# DBL_TLC5940_driver_for_High_load_-_5_3A_.net
KiCad netlist of a schematic drawn in Altium Designer
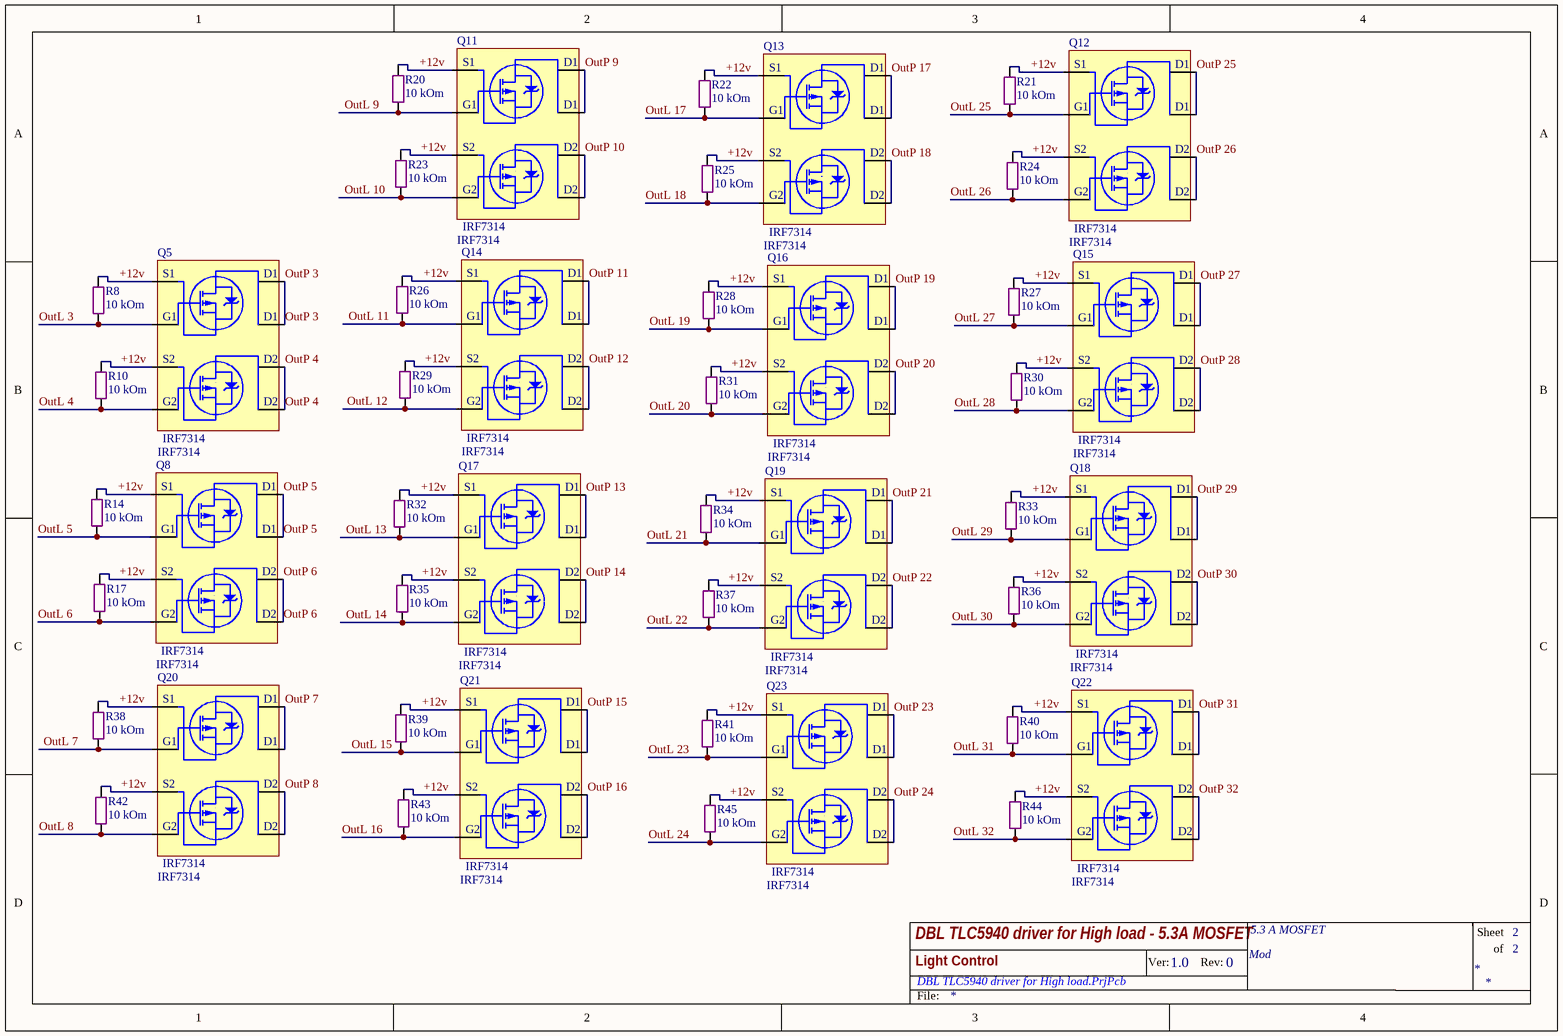
[diagram p0: DBL TLC5940 driver for High load - 5.3A MOSFET.SchDoc]

(export (version "E")
  (design (tool "Eeschema 10.0.6"))
  (components
    (comp (ref "Q5")
      (value "IRF7314")
      (footprint "GeneralCases:SO8")
      (description "Dual P-Ch  20V - 0.058Ω - 5.3A")
      (libsource (lib "Transistor") (part "IRF7314"))
    )
    (comp (ref "Q8")
      (value "IRF7314")
      (footprint "GeneralCases:SO8")
      (description "Dual P-Ch  20V - 0.058Ω - 5.3A")
      (libsource (lib "Transistor") (part "IRF7314"))
    )
    (comp (ref "Q11")
      (value "IRF7314")
      (footprint "GeneralCases:SO8")
      (description "Dual P-Ch  20V - 0.058Ω - 5.3A")
      (libsource (lib "Transistor") (part "IRF7314"))
    )
    (comp (ref "Q12")
      (value "IRF7314")
      (footprint "GeneralCases:SO8")
      (description "Dual P-Ch  20V - 0.058Ω - 5.3A")
      (libsource (lib "Transistor") (part "IRF7314"))
    )
    (comp (ref "Q13")
      (value "IRF7314")
      (footprint "GeneralCases:SO8")
      (description "Dual P-Ch  20V - 0.058Ω - 5.3A")
      (libsource (lib "Transistor") (part "IRF7314"))
    )
    (comp (ref "Q14")
      (value "IRF7314")
      (footprint "GeneralCases:SO8")
      (description "Dual P-Ch  20V - 0.058Ω - 5.3A")
      (libsource (lib "Transistor") (part "IRF7314"))
    )
    (comp (ref "Q15")
      (value "IRF7314")
      (footprint "GeneralCases:SO8")
      (description "Dual P-Ch  20V - 0.058Ω - 5.3A")
      (libsource (lib "Transistor") (part "IRF7314"))
    )
    (comp (ref "Q16")
      (value "IRF7314")
      (footprint "GeneralCases:SO8")
      (description "Dual P-Ch  20V - 0.058Ω - 5.3A")
      (libsource (lib "Transistor") (part "IRF7314"))
    )
    (comp (ref "Q17")
      (value "IRF7314")
      (footprint "GeneralCases:SO8")
      (description "Dual P-Ch  20V - 0.058Ω - 5.3A")
      (libsource (lib "Transistor") (part "IRF7314"))
    )
    (comp (ref "Q18")
      (value "IRF7314")
      (footprint "GeneralCases:SO8")
      (description "Dual P-Ch  20V - 0.058Ω - 5.3A")
      (libsource (lib "Transistor") (part "IRF7314"))
    )
    (comp (ref "Q19")
      (value "IRF7314")
      (footprint "GeneralCases:SO8")
      (description "Dual P-Ch  20V - 0.058Ω - 5.3A")
      (libsource (lib "Transistor") (part "IRF7314"))
    )
    (comp (ref "Q20")
      (value "IRF7314")
      (footprint "GeneralCases:SO8")
      (description "Dual P-Ch  20V - 0.058Ω - 5.3A")
      (libsource (lib "Transistor") (part "IRF7314"))
    )
    (comp (ref "Q21")
      (value "IRF7314")
      (footprint "GeneralCases:SO8")
      (description "Dual P-Ch  20V - 0.058Ω - 5.3A")
      (libsource (lib "Transistor") (part "IRF7314"))
    )
    (comp (ref "Q22")
      (value "IRF7314")
      (footprint "GeneralCases:SO8")
      (description "Dual P-Ch  20V - 0.058Ω - 5.3A")
      (libsource (lib "Transistor") (part "IRF7314"))
    )
    (comp (ref "Q23")
      (value "IRF7314")
      (footprint "GeneralCases:SO8")
      (description "Dual P-Ch  20V - 0.058Ω - 5.3A")
      (libsource (lib "Transistor") (part "IRF7314"))
    )
    (comp (ref "R8")
      (value "10 kOm")
      (footprint "PassiveComponents:SMD 0805 (2012)")
      (libsource (lib "PassiveComponents") (part "Res All Types"))
    )
    (comp (ref "R10")
      (value "10 kOm")
      (footprint "PassiveComponents:SMD 0805 (2012)")
      (libsource (lib "PassiveComponents") (part "Res All Types"))
    )
    (comp (ref "R14")
      (value "10 kOm")
      (footprint "PassiveComponents:SMD 0805 (2012)")
      (libsource (lib "PassiveComponents") (part "Res All Types"))
    )
    (comp (ref "R17")
      (value "10 kOm")
      (footprint "PassiveComponents:SMD 0805 (2012)")
      (libsource (lib "PassiveComponents") (part "Res All Types"))
    )
    (comp (ref "R20")
      (value "10 kOm")
      (footprint "PassiveComponents:SMD 0805 (2012)")
      (libsource (lib "PassiveComponents") (part "Res All Types"))
    )
    (comp (ref "R21")
      (value "10 kOm")
      (footprint "PassiveComponents:SMD 0805 (2012)")
      (libsource (lib "PassiveComponents") (part "Res All Types"))
    )
    (comp (ref "R22")
      (value "10 kOm")
      (footprint "PassiveComponents:SMD 0805 (2012)")
      (libsource (lib "PassiveComponents") (part "Res All Types"))
    )
    (comp (ref "R23")
      (value "10 kOm")
      (footprint "PassiveComponents:SMD 0805 (2012)")
      (libsource (lib "PassiveComponents") (part "Res All Types"))
    )
    (comp (ref "R24")
      (value "10 kOm")
      (footprint "PassiveComponents:SMD 0805 (2012)")
      (libsource (lib "PassiveComponents") (part "Res All Types"))
    )
    (comp (ref "R25")
      (value "10 kOm")
      (footprint "PassiveComponents:SMD 0805 (2012)")
      (libsource (lib "PassiveComponents") (part "Res All Types"))
    )
    (comp (ref "R26")
      (value "10 kOm")
      (footprint "PassiveComponents:SMD 0805 (2012)")
      (libsource (lib "PassiveComponents") (part "Res All Types"))
    )
    (comp (ref "R27")
      (value "10 kOm")
      (footprint "PassiveComponents:SMD 0805 (2012)")
      (libsource (lib "PassiveComponents") (part "Res All Types"))
    )
    (comp (ref "R28")
      (value "10 kOm")
      (footprint "PassiveComponents:SMD 0805 (2012)")
      (libsource (lib "PassiveComponents") (part "Res All Types"))
    )
    (comp (ref "R29")
      (value "10 kOm")
      (footprint "PassiveComponents:SMD 0805 (2012)")
      (libsource (lib "PassiveComponents") (part "Res All Types"))
    )
    (comp (ref "R30")
      (value "10 kOm")
      (footprint "PassiveComponents:SMD 0805 (2012)")
      (libsource (lib "PassiveComponents") (part "Res All Types"))
    )
    (comp (ref "R31")
      (value "10 kOm")
      (footprint "PassiveComponents:SMD 0805 (2012)")
      (libsource (lib "PassiveComponents") (part "Res All Types"))
    )
    (comp (ref "R32")
      (value "10 kOm")
      (footprint "PassiveComponents:SMD 0805 (2012)")
      (libsource (lib "PassiveComponents") (part "Res All Types"))
    )
    (comp (ref "R33")
      (value "10 kOm")
      (footprint "PassiveComponents:SMD 0805 (2012)")
      (libsource (lib "PassiveComponents") (part "Res All Types"))
    )
    (comp (ref "R34")
      (value "10 kOm")
      (footprint "PassiveComponents:SMD 0805 (2012)")
      (libsource (lib "PassiveComponents") (part "Res All Types"))
    )
    (comp (ref "R35")
      (value "10 kOm")
      (footprint "PassiveComponents:SMD 0805 (2012)")
      (libsource (lib "PassiveComponents") (part "Res All Types"))
    )
    (comp (ref "R36")
      (value "10 kOm")
      (footprint "PassiveComponents:SMD 0805 (2012)")
      (libsource (lib "PassiveComponents") (part "Res All Types"))
    )
    (comp (ref "R37")
      (value "10 kOm")
      (footprint "PassiveComponents:SMD 0805 (2012)")
      (libsource (lib "PassiveComponents") (part "Res All Types"))
    )
    (comp (ref "R38")
      (value "10 kOm")
      (footprint "PassiveComponents:SMD 0805 (2012)")
      (libsource (lib "PassiveComponents") (part "Res All Types"))
    )
    (comp (ref "R39")
      (value "10 kOm")
      (footprint "PassiveComponents:SMD 0805 (2012)")
      (libsource (lib "PassiveComponents") (part "Res All Types"))
    )
    (comp (ref "R40")
      (value "10 kOm")
      (footprint "PassiveComponents:SMD 0805 (2012)")
      (libsource (lib "PassiveComponents") (part "Res All Types"))
    )
    (comp (ref "R41")
      (value "10 kOm")
      (footprint "PassiveComponents:SMD 0805 (2012)")
      (libsource (lib "PassiveComponents") (part "Res All Types"))
    )
    (comp (ref "R42")
      (value "10 kOm")
      (footprint "PassiveComponents:SMD 0805 (2012)")
      (libsource (lib "PassiveComponents") (part "Res All Types"))
    )
    (comp (ref "R43")
      (value "10 kOm")
      (footprint "PassiveComponents:SMD 0805 (2012)")
      (libsource (lib "PassiveComponents") (part "Res All Types"))
    )
    (comp (ref "R44")
      (value "10 kOm")
      (footprint "PassiveComponents:SMD 0805 (2012)")
      (libsource (lib "PassiveComponents") (part "Res All Types"))
    )
    (comp (ref "R45")
      (value "10 kOm")
      (footprint "PassiveComponents:SMD 0805 (2012)")
      (libsource (lib "PassiveComponents") (part "Res All Types"))
    )
  )
  (nets
    (net (code "1") (name "/+12v") (class "Default")
      (node (ref "Q11") (pin "1") (pinfunction "S_1") (pintype "passive"))
      (node (ref "Q11") (pin "3") (pinfunction "S_3") (pintype "passive"))
      (node (ref "Q12") (pin "1") (pinfunction "S_1") (pintype "passive"))
      (node (ref "Q12") (pin "3") (pinfunction "S_3") (pintype "passive"))
      (node (ref "Q13") (pin "1") (pinfunction "S_1") (pintype "passive"))
      (node (ref "Q13") (pin "3") (pinfunction "S_3") (pintype "passive"))
      (node (ref "Q14") (pin "1") (pinfunction "S_1") (pintype "passive"))
      (node (ref "Q14") (pin "3") (pinfunction "S_3") (pintype "passive"))
      (node (ref "Q15") (pin "1") (pinfunction "S_1") (pintype "passive"))
      (node (ref "Q15") (pin "3") (pinfunction "S_3") (pintype "passive"))
      (node (ref "Q16") (pin "1") (pinfunction "S_1") (pintype "passive"))
      (node (ref "Q16") (pin "3") (pinfunction "S_3") (pintype "passive"))
      (node (ref "Q17") (pin "1") (pinfunction "S_1") (pintype "passive"))
      (node (ref "Q17") (pin "3") (pinfunction "S_3") (pintype "passive"))
      (node (ref "Q18") (pin "1") (pinfunction "S_1") (pintype "passive"))
      (node (ref "Q18") (pin "3") (pinfunction "S_3") (pintype "passive"))
      (node (ref "Q19") (pin "1") (pinfunction "S_1") (pintype "passive"))
      (node (ref "Q19") (pin "3") (pinfunction "S_3") (pintype "passive"))
      (node (ref "Q20") (pin "1") (pinfunction "S_1") (pintype "passive"))
      (node (ref "Q20") (pin "3") (pinfunction "S_3") (pintype "passive"))
      (node (ref "Q21") (pin "1") (pinfunction "S_1") (pintype "passive"))
      (node (ref "Q21") (pin "3") (pinfunction "S_3") (pintype "passive"))
      (node (ref "Q22") (pin "1") (pinfunction "S_1") (pintype "passive"))
      (node (ref "Q22") (pin "3") (pinfunction "S_3") (pintype "passive"))
      (node (ref "Q23") (pin "1") (pinfunction "S_1") (pintype "passive"))
      (node (ref "Q23") (pin "3") (pinfunction "S_3") (pintype "passive"))
      (node (ref "Q5") (pin "1") (pinfunction "S_1") (pintype "passive"))
      (node (ref "Q5") (pin "3") (pinfunction "S_3") (pintype "passive"))
      (node (ref "Q8") (pin "1") (pinfunction "S_1") (pintype "passive"))
      (node (ref "Q8") (pin "3") (pinfunction "S_3") (pintype "passive"))
      (node (ref "R10") (pin "2") (pinfunction "2_2") (pintype "passive"))
      (node (ref "R14") (pin "2") (pinfunction "2_2") (pintype "passive"))
      (node (ref "R17") (pin "2") (pinfunction "2_2") (pintype "passive"))
      (node (ref "R20") (pin "2") (pinfunction "2_2") (pintype "passive"))
      (node (ref "R21") (pin "2") (pinfunction "2_2") (pintype "passive"))
      (node (ref "R22") (pin "2") (pinfunction "2_2") (pintype "passive"))
      (node (ref "R23") (pin "2") (pinfunction "2_2") (pintype "passive"))
      (node (ref "R24") (pin "2") (pinfunction "2_2") (pintype "passive"))
      (node (ref "R25") (pin "2") (pinfunction "2_2") (pintype "passive"))
      (node (ref "R26") (pin "2") (pinfunction "2_2") (pintype "passive"))
      (node (ref "R27") (pin "2") (pinfunction "2_2") (pintype "passive"))
      (node (ref "R28") (pin "2") (pinfunction "2_2") (pintype "passive"))
      (node (ref "R29") (pin "2") (pinfunction "2_2") (pintype "passive"))
      (node (ref "R30") (pin "2") (pinfunction "2_2") (pintype "passive"))
      (node (ref "R31") (pin "2") (pinfunction "2_2") (pintype "passive"))
      (node (ref "R32") (pin "2") (pinfunction "2_2") (pintype "passive"))
      (node (ref "R33") (pin "2") (pinfunction "2_2") (pintype "passive"))
      (node (ref "R34") (pin "2") (pinfunction "2_2") (pintype "passive"))
      (node (ref "R35") (pin "2") (pinfunction "2_2") (pintype "passive"))
      (node (ref "R36") (pin "2") (pinfunction "2_2") (pintype "passive"))
      (node (ref "R37") (pin "2") (pinfunction "2_2") (pintype "passive"))
      (node (ref "R38") (pin "2") (pinfunction "2_2") (pintype "passive"))
      (node (ref "R39") (pin "2") (pinfunction "2_2") (pintype "passive"))
      (node (ref "R40") (pin "2") (pinfunction "2_2") (pintype "passive"))
      (node (ref "R41") (pin "2") (pinfunction "2_2") (pintype "passive"))
      (node (ref "R42") (pin "2") (pinfunction "2_2") (pintype "passive"))
      (node (ref "R43") (pin "2") (pinfunction "2_2") (pintype "passive"))
      (node (ref "R44") (pin "2") (pinfunction "2_2") (pintype "passive"))
      (node (ref "R45") (pin "2") (pinfunction "2_2") (pintype "passive"))
      (node (ref "R8") (pin "2") (pinfunction "2_2") (pintype "passive"))
    )
    (net (code "2") (name "/OutL 3") (class "Default")
      (node (ref "Q5") (pin "2") (pinfunction "G_2") (pintype "passive"))
      (node (ref "R8") (pin "1") (pinfunction "1_1") (pintype "passive"))
    )
    (net (code "3") (name "/OutL 4") (class "Default")
      (node (ref "Q5") (pin "4") (pinfunction "G_4") (pintype "passive"))
      (node (ref "R10") (pin "1") (pinfunction "1_1") (pintype "passive"))
    )
    (net (code "4") (name "/OutL 5") (class "Default")
      (node (ref "Q8") (pin "2") (pinfunction "G_2") (pintype "passive"))
      (node (ref "R14") (pin "1") (pinfunction "1_1") (pintype "passive"))
    )
    (net (code "5") (name "/OutL 6") (class "Default")
      (node (ref "Q8") (pin "4") (pinfunction "G_4") (pintype "passive"))
      (node (ref "R17") (pin "1") (pinfunction "1_1") (pintype "passive"))
    )
    (net (code "6") (name "/OutL 7") (class "Default")
      (node (ref "Q20") (pin "2") (pinfunction "G_2") (pintype "passive"))
      (node (ref "R38") (pin "1") (pinfunction "1_1") (pintype "passive"))
    )
    (net (code "7") (name "/OutL 8") (class "Default")
      (node (ref "Q20") (pin "4") (pinfunction "G_4") (pintype "passive"))
      (node (ref "R42") (pin "1") (pinfunction "1_1") (pintype "passive"))
    )
    (net (code "8") (name "/OutL 9") (class "Default")
      (node (ref "Q11") (pin "2") (pinfunction "G_2") (pintype "passive"))
      (node (ref "R20") (pin "1") (pinfunction "1_1") (pintype "passive"))
    )
    (net (code "9") (name "/OutL 10") (class "Default")
      (node (ref "Q11") (pin "4") (pinfunction "G_4") (pintype "passive"))
      (node (ref "R23") (pin "1") (pinfunction "1_1") (pintype "passive"))
    )
    (net (code "10") (name "/OutL 11") (class "Default")
      (node (ref "Q14") (pin "2") (pinfunction "G_2") (pintype "passive"))
      (node (ref "R26") (pin "1") (pinfunction "1_1") (pintype "passive"))
    )
    (net (code "11") (name "/OutL 12") (class "Default")
      (node (ref "Q14") (pin "4") (pinfunction "G_4") (pintype "passive"))
      (node (ref "R29") (pin "1") (pinfunction "1_1") (pintype "passive"))
    )
    (net (code "12") (name "/OutL 13") (class "Default")
      (node (ref "Q17") (pin "2") (pinfunction "G_2") (pintype "passive"))
      (node (ref "R32") (pin "1") (pinfunction "1_1") (pintype "passive"))
    )
    (net (code "13") (name "/OutL 14") (class "Default")
      (node (ref "Q17") (pin "4") (pinfunction "G_4") (pintype "passive"))
      (node (ref "R35") (pin "1") (pinfunction "1_1") (pintype "passive"))
    )
    (net (code "14") (name "/OutL 15") (class "Default")
      (node (ref "Q21") (pin "2") (pinfunction "G_2") (pintype "passive"))
      (node (ref "R39") (pin "1") (pinfunction "1_1") (pintype "passive"))
    )
    (net (code "15") (name "/OutL 16") (class "Default")
      (node (ref "Q21") (pin "4") (pinfunction "G_4") (pintype "passive"))
      (node (ref "R43") (pin "1") (pinfunction "1_1") (pintype "passive"))
    )
    (net (code "16") (name "/OutL 17") (class "Default")
      (node (ref "Q13") (pin "2") (pinfunction "G_2") (pintype "passive"))
      (node (ref "R22") (pin "1") (pinfunction "1_1") (pintype "passive"))
    )
    (net (code "17") (name "/OutL 18") (class "Default")
      (node (ref "Q13") (pin "4") (pinfunction "G_4") (pintype "passive"))
      (node (ref "R25") (pin "1") (pinfunction "1_1") (pintype "passive"))
    )
    (net (code "18") (name "/OutL 19") (class "Default")
      (node (ref "Q16") (pin "2") (pinfunction "G_2") (pintype "passive"))
      (node (ref "R28") (pin "1") (pinfunction "1_1") (pintype "passive"))
    )
    (net (code "19") (name "/OutL 20") (class "Default")
      (node (ref "Q16") (pin "4") (pinfunction "G_4") (pintype "passive"))
      (node (ref "R31") (pin "1") (pinfunction "1_1") (pintype "passive"))
    )
    (net (code "20") (name "/OutL 21") (class "Default")
      (node (ref "Q19") (pin "2") (pinfunction "G_2") (pintype "passive"))
      (node (ref "R34") (pin "1") (pinfunction "1_1") (pintype "passive"))
    )
    (net (code "21") (name "/OutL 22") (class "Default")
      (node (ref "Q19") (pin "4") (pinfunction "G_4") (pintype "passive"))
      (node (ref "R37") (pin "1") (pinfunction "1_1") (pintype "passive"))
    )
    (net (code "22") (name "/OutL 23") (class "Default")
      (node (ref "Q23") (pin "2") (pinfunction "G_2") (pintype "passive"))
      (node (ref "R41") (pin "1") (pinfunction "1_1") (pintype "passive"))
    )
    (net (code "23") (name "/OutL 24") (class "Default")
      (node (ref "Q23") (pin "4") (pinfunction "G_4") (pintype "passive"))
      (node (ref "R45") (pin "1") (pinfunction "1_1") (pintype "passive"))
    )
    (net (code "24") (name "/OutL 25") (class "Default")
      (node (ref "Q12") (pin "2") (pinfunction "G_2") (pintype "passive"))
      (node (ref "R21") (pin "1") (pinfunction "1_1") (pintype "passive"))
    )
    (net (code "25") (name "/OutL 26") (class "Default")
      (node (ref "Q12") (pin "4") (pinfunction "G_4") (pintype "passive"))
      (node (ref "R24") (pin "1") (pinfunction "1_1") (pintype "passive"))
    )
    (net (code "26") (name "/OutL 27") (class "Default")
      (node (ref "Q15") (pin "2") (pinfunction "G_2") (pintype "passive"))
      (node (ref "R27") (pin "1") (pinfunction "1_1") (pintype "passive"))
    )
    (net (code "27") (name "/OutL 28") (class "Default")
      (node (ref "Q15") (pin "4") (pinfunction "G_4") (pintype "passive"))
      (node (ref "R30") (pin "1") (pinfunction "1_1") (pintype "passive"))
    )
    (net (code "28") (name "/OutL 29") (class "Default")
      (node (ref "Q18") (pin "2") (pinfunction "G_2") (pintype "passive"))
      (node (ref "R33") (pin "1") (pinfunction "1_1") (pintype "passive"))
    )
    (net (code "29") (name "/OutL 30") (class "Default")
      (node (ref "Q18") (pin "4") (pinfunction "G_4") (pintype "passive"))
      (node (ref "R36") (pin "1") (pinfunction "1_1") (pintype "passive"))
    )
    (net (code "30") (name "/OutL 31") (class "Default")
      (node (ref "Q22") (pin "2") (pinfunction "G_2") (pintype "passive"))
      (node (ref "R40") (pin "1") (pinfunction "1_1") (pintype "passive"))
    )
    (net (code "31") (name "/OutL 32") (class "Default")
      (node (ref "Q22") (pin "4") (pinfunction "G_4") (pintype "passive"))
      (node (ref "R44") (pin "1") (pinfunction "1_1") (pintype "passive"))
    )
    (net (code "32") (name "/OutP 3") (class "Default")
      (node (ref "Q5") (pin "7") (pinfunction "D_7") (pintype "passive"))
      (node (ref "Q5") (pin "8") (pinfunction "D_8") (pintype "passive"))
    )
    (net (code "33") (name "/OutP 4") (class "Default")
      (node (ref "Q5") (pin "5") (pinfunction "D_5") (pintype "passive"))
      (node (ref "Q5") (pin "6") (pinfunction "D_6") (pintype "passive"))
    )
    (net (code "34") (name "/OutP 5") (class "Default")
      (node (ref "Q8") (pin "7") (pinfunction "D_7") (pintype "passive"))
      (node (ref "Q8") (pin "8") (pinfunction "D_8") (pintype "passive"))
    )
    (net (code "35") (name "/OutP 6") (class "Default")
      (node (ref "Q8") (pin "5") (pinfunction "D_5") (pintype "passive"))
      (node (ref "Q8") (pin "6") (pinfunction "D_6") (pintype "passive"))
    )
    (net (code "36") (name "/OutP 7") (class "Default")
      (node (ref "Q20") (pin "7") (pinfunction "D_7") (pintype "passive"))
      (node (ref "Q20") (pin "8") (pinfunction "D_8") (pintype "passive"))
    )
    (net (code "37") (name "/OutP 8") (class "Default")
      (node (ref "Q20") (pin "5") (pinfunction "D_5") (pintype "passive"))
      (node (ref "Q20") (pin "6") (pinfunction "D_6") (pintype "passive"))
    )
    (net (code "38") (name "/OutP 9") (class "Default")
      (node (ref "Q11") (pin "7") (pinfunction "D_7") (pintype "passive"))
      (node (ref "Q11") (pin "8") (pinfunction "D_8") (pintype "passive"))
    )
    (net (code "39") (name "/OutP 10") (class "Default")
      (node (ref "Q11") (pin "5") (pinfunction "D_5") (pintype "passive"))
      (node (ref "Q11") (pin "6") (pinfunction "D_6") (pintype "passive"))
    )
    (net (code "40") (name "/OutP 11") (class "Default")
      (node (ref "Q14") (pin "7") (pinfunction "D_7") (pintype "passive"))
      (node (ref "Q14") (pin "8") (pinfunction "D_8") (pintype "passive"))
    )
    (net (code "41") (name "/OutP 12") (class "Default")
      (node (ref "Q14") (pin "5") (pinfunction "D_5") (pintype "passive"))
      (node (ref "Q14") (pin "6") (pinfunction "D_6") (pintype "passive"))
    )
    (net (code "42") (name "/OutP 13") (class "Default")
      (node (ref "Q17") (pin "7") (pinfunction "D_7") (pintype "passive"))
      (node (ref "Q17") (pin "8") (pinfunction "D_8") (pintype "passive"))
    )
    (net (code "43") (name "/OutP 14") (class "Default")
      (node (ref "Q17") (pin "5") (pinfunction "D_5") (pintype "passive"))
      (node (ref "Q17") (pin "6") (pinfunction "D_6") (pintype "passive"))
    )
    (net (code "44") (name "/OutP 15") (class "Default")
      (node (ref "Q21") (pin "7") (pinfunction "D_7") (pintype "passive"))
      (node (ref "Q21") (pin "8") (pinfunction "D_8") (pintype "passive"))
    )
    (net (code "45") (name "/OutP 16") (class "Default")
      (node (ref "Q21") (pin "5") (pinfunction "D_5") (pintype "passive"))
      (node (ref "Q21") (pin "6") (pinfunction "D_6") (pintype "passive"))
    )
    (net (code "46") (name "/OutP 17") (class "Default")
      (node (ref "Q13") (pin "7") (pinfunction "D_7") (pintype "passive"))
      (node (ref "Q13") (pin "8") (pinfunction "D_8") (pintype "passive"))
    )
    (net (code "47") (name "/OutP 18") (class "Default")
      (node (ref "Q13") (pin "5") (pinfunction "D_5") (pintype "passive"))
      (node (ref "Q13") (pin "6") (pinfunction "D_6") (pintype "passive"))
    )
    (net (code "48") (name "/OutP 19") (class "Default")
      (node (ref "Q16") (pin "7") (pinfunction "D_7") (pintype "passive"))
      (node (ref "Q16") (pin "8") (pinfunction "D_8") (pintype "passive"))
    )
    (net (code "49") (name "/OutP 20") (class "Default")
      (node (ref "Q16") (pin "5") (pinfunction "D_5") (pintype "passive"))
      (node (ref "Q16") (pin "6") (pinfunction "D_6") (pintype "passive"))
    )
    (net (code "50") (name "/OutP 21") (class "Default")
      (node (ref "Q19") (pin "7") (pinfunction "D_7") (pintype "passive"))
      (node (ref "Q19") (pin "8") (pinfunction "D_8") (pintype "passive"))
    )
    (net (code "51") (name "/OutP 22") (class "Default")
      (node (ref "Q19") (pin "5") (pinfunction "D_5") (pintype "passive"))
      (node (ref "Q19") (pin "6") (pinfunction "D_6") (pintype "passive"))
    )
    (net (code "52") (name "/OutP 23") (class "Default")
      (node (ref "Q23") (pin "7") (pinfunction "D_7") (pintype "passive"))
      (node (ref "Q23") (pin "8") (pinfunction "D_8") (pintype "passive"))
    )
    (net (code "53") (name "/OutP 24") (class "Default")
      (node (ref "Q23") (pin "5") (pinfunction "D_5") (pintype "passive"))
      (node (ref "Q23") (pin "6") (pinfunction "D_6") (pintype "passive"))
    )
    (net (code "54") (name "/OutP 25") (class "Default")
      (node (ref "Q12") (pin "7") (pinfunction "D_7") (pintype "passive"))
      (node (ref "Q12") (pin "8") (pinfunction "D_8") (pintype "passive"))
    )
    (net (code "55") (name "/OutP 26") (class "Default")
      (node (ref "Q12") (pin "5") (pinfunction "D_5") (pintype "passive"))
      (node (ref "Q12") (pin "6") (pinfunction "D_6") (pintype "passive"))
    )
    (net (code "56") (name "/OutP 27") (class "Default")
      (node (ref "Q15") (pin "7") (pinfunction "D_7") (pintype "passive"))
      (node (ref "Q15") (pin "8") (pinfunction "D_8") (pintype "passive"))
    )
    (net (code "57") (name "/OutP 28") (class "Default")
      (node (ref "Q15") (pin "5") (pinfunction "D_5") (pintype "passive"))
      (node (ref "Q15") (pin "6") (pinfunction "D_6") (pintype "passive"))
    )
    (net (code "58") (name "/OutP 29") (class "Default")
      (node (ref "Q18") (pin "7") (pinfunction "D_7") (pintype "passive"))
      (node (ref "Q18") (pin "8") (pinfunction "D_8") (pintype "passive"))
    )
    (net (code "59") (name "/OutP 30") (class "Default")
      (node (ref "Q18") (pin "5") (pinfunction "D_5") (pintype "passive"))
      (node (ref "Q18") (pin "6") (pinfunction "D_6") (pintype "passive"))
    )
    (net (code "60") (name "/OutP 31") (class "Default")
      (node (ref "Q22") (pin "7") (pinfunction "D_7") (pintype "passive"))
      (node (ref "Q22") (pin "8") (pinfunction "D_8") (pintype "passive"))
    )
    (net (code "61") (name "/OutP 32") (class "Default")
      (node (ref "Q22") (pin "5") (pinfunction "D_5") (pintype "passive"))
      (node (ref "Q22") (pin "6") (pinfunction "D_6") (pintype "passive"))
    )
  )
)
